# SHIELD4.net
KiCad netlist of a schematic drawn in Altium Designer
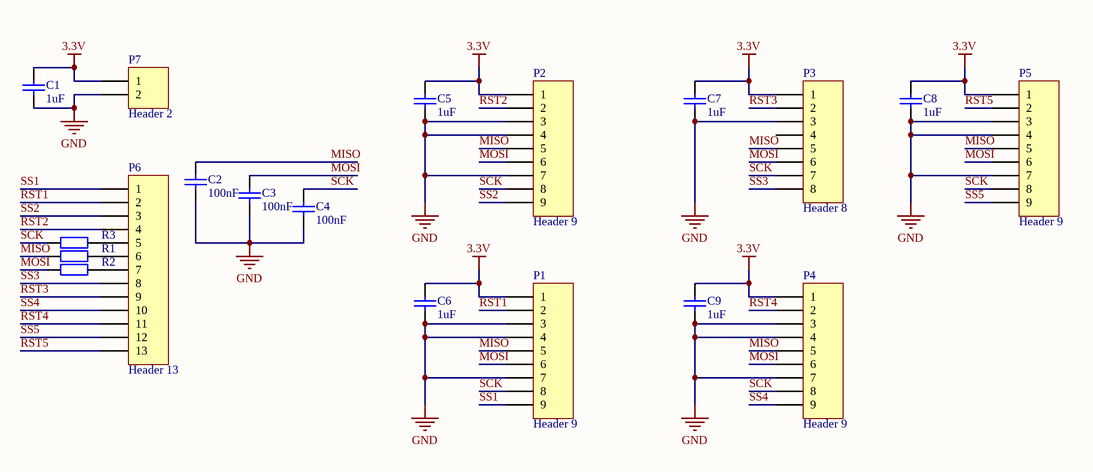
[diagram p0: SHIELD4.SchDoc]

(export (version "E")
  (design (tool "Eeschema 10.0.6"))
  (components
    (comp (ref "C1")
      (value "1uF")
      (footprint "C0805")
      (description "Capacitor")
      (fields (field (name "Comment") "Cap") (field (name "PUBLISHER") "Altium Limited"))
      (libsource (lib "Library") (part "Cap"))
    )
    (comp (ref "C2")
      (value "100nF")
      (footprint "C0805")
      (description "Capacitor")
      (fields (field (name "Comment") "Cap") (field (name "PUBLISHER") "Altium Limited"))
      (libsource (lib "Library") (part "Cap"))
    )
    (comp (ref "C3")
      (value "100nF")
      (footprint "C0805")
      (description "Capacitor")
      (fields (field (name "Comment") "Cap") (field (name "PUBLISHER") "Altium Limited"))
      (libsource (lib "Library") (part "Cap"))
    )
    (comp (ref "C4")
      (value "100nF")
      (footprint "C0805")
      (description "Capacitor")
      (fields (field (name "Comment") "Cap") (field (name "PUBLISHER") "Altium Limited"))
      (libsource (lib "Library") (part "Cap"))
    )
    (comp (ref "C5")
      (value "1uF")
      (footprint "C0805")
      (description "Capacitor")
      (fields (field (name "Comment") "Cap") (field (name "PUBLISHER") "Altium Limited"))
      (libsource (lib "Library") (part "Cap"))
    )
    (comp (ref "C6")
      (value "1uF")
      (footprint "C0805")
      (description "Capacitor")
      (fields (field (name "Comment") "Cap") (field (name "PUBLISHER") "Altium Limited"))
      (libsource (lib "Library") (part "Cap"))
    )
    (comp (ref "C7")
      (value "1uF")
      (footprint "C0805")
      (description "Capacitor")
      (fields (field (name "Comment") "Cap") (field (name "PUBLISHER") "Altium Limited"))
      (libsource (lib "Library") (part "Cap"))
    )
    (comp (ref "C8")
      (value "1uF")
      (footprint "C0805")
      (description "Capacitor")
      (fields (field (name "Comment") "Cap") (field (name "PUBLISHER") "Altium Limited"))
      (libsource (lib "Library") (part "Cap"))
    )
    (comp (ref "C9")
      (value "1uF")
      (footprint "C0805")
      (description "Capacitor")
      (fields (field (name "Comment") "Cap") (field (name "PUBLISHER") "Altium Limited"))
      (libsource (lib "Library") (part "Cap"))
    )
    (comp (ref "P1")
      (value "Header 9")
      (footprint "HDR1X9")
      (description "Header, 9-Pin")
      (fields (field (name "PUBLISHER") "Altium Limited"))
      (libsource (lib "Miscellaneous Connectors") (part "Header 9"))
    )
    (comp (ref "P2")
      (value "Header 9")
      (footprint "HDR1X9")
      (description "Header, 9-Pin")
      (fields (field (name "PUBLISHER") "Altium Limited"))
      (libsource (lib "Miscellaneous Connectors") (part "Header 9"))
    )
    (comp (ref "P3")
      (value "Header 8")
      (footprint "HDR1X8")
      (description "Header, 8-Pin")
      (fields (field (name "PUBLISHER") "Altium Limited"))
      (libsource (lib "Miscellaneous Connectors") (part "Header 8"))
    )
    (comp (ref "P4")
      (value "Header 9")
      (footprint "HDR1X9")
      (description "Header, 9-Pin")
      (fields (field (name "PUBLISHER") "Altium Limited"))
      (libsource (lib "Miscellaneous Connectors") (part "Header 9"))
    )
    (comp (ref "P5")
      (value "Header 9")
      (footprint "HDR1X9")
      (description "Header, 9-Pin")
      (fields (field (name "PUBLISHER") "Altium Limited"))
      (libsource (lib "Miscellaneous Connectors") (part "Header 9"))
    )
    (comp (ref "P6")
      (value "Header 13")
      (footprint "HDR1X13")
      (description "Header, 13-Pin")
      (fields (field (name "PUBLISHER") "Altium Limited"))
      (libsource (lib "Miscellaneous Connectors") (part "Header 13"))
    )
    (comp (ref "P7")
      (value "Header 2")
      (footprint "HDR1X2")
      (description "Header, 2-Pin")
      (fields (field (name "PUBLISHER") "Altium Limited"))
      (libsource (lib "Miscellaneous Connectors") (part "Header 2"))
    )
    (comp (ref "R1")
      (value "Res2")
      (footprint "6-0805_N")
      (description "Resistor")
      (fields (field (name "PUBLISHER") "Altium Limited"))
      (libsource (lib "Library") (part "Res2"))
    )
    (comp (ref "R2")
      (value "Res2")
      (footprint "6-0805_N")
      (description "Resistor")
      (fields (field (name "PUBLISHER") "Altium Limited"))
      (libsource (lib "Library") (part "Res2"))
    )
    (comp (ref "R3")
      (value "Res2")
      (footprint "6-0805_N")
      (description "Resistor")
      (fields (field (name "PUBLISHER") "Altium Limited"))
      (libsource (lib "Library") (part "Res2"))
    )
  )
  (nets
    (net (code "1") (name "/MISO") (class "Default")
      (node (ref "C2") (pin "2") (pinfunction "2_2") (pintype "passive"))
      (node (ref "P1") (pin "5") (pinfunction "5_5") (pintype "passive"))
      (node (ref "P2") (pin "5") (pinfunction "5_5") (pintype "passive"))
      (node (ref "P3") (pin "5") (pinfunction "5_5") (pintype "passive"))
      (node (ref "P4") (pin "5") (pinfunction "5_5") (pintype "passive"))
      (node (ref "P5") (pin "5") (pinfunction "5_5") (pintype "passive"))
      (node (ref "R1") (pin "1") (pinfunction "1_1") (pintype "passive"))
    )
    (net (code "2") (name "/MOSI") (class "Default")
      (node (ref "C3") (pin "1") (pinfunction "1_1") (pintype "passive"))
      (node (ref "P1") (pin "6") (pinfunction "6_6") (pintype "passive"))
      (node (ref "P2") (pin "6") (pinfunction "6_6") (pintype "passive"))
      (node (ref "P3") (pin "6") (pinfunction "6_6") (pintype "passive"))
      (node (ref "P4") (pin "6") (pinfunction "6_6") (pintype "passive"))
      (node (ref "P5") (pin "6") (pinfunction "6_6") (pintype "passive"))
      (node (ref "R2") (pin "1") (pinfunction "1_1") (pintype "passive"))
    )
    (net (code "3") (name "/RST1") (class "Default")
      (node (ref "P1") (pin "2") (pinfunction "2_2") (pintype "passive"))
      (node (ref "P6") (pin "2") (pinfunction "2_2") (pintype "passive"))
    )
    (net (code "4") (name "/RST2") (class "Default")
      (node (ref "P2") (pin "2") (pinfunction "2_2") (pintype "passive"))
      (node (ref "P6") (pin "4") (pinfunction "4_4") (pintype "passive"))
    )
    (net (code "5") (name "/RST3") (class "Default")
      (node (ref "P3") (pin "2") (pinfunction "2_2") (pintype "passive"))
      (node (ref "P6") (pin "9") (pinfunction "9_9") (pintype "passive"))
    )
    (net (code "6") (name "/RST4") (class "Default")
      (node (ref "P4") (pin "2") (pinfunction "2_2") (pintype "passive"))
      (node (ref "P6") (pin "11") (pinfunction "11_11") (pintype "passive"))
    )
    (net (code "7") (name "/RST5") (class "Default")
      (node (ref "P5") (pin "2") (pinfunction "2_2") (pintype "passive"))
      (node (ref "P6") (pin "13") (pinfunction "13_13") (pintype "passive"))
    )
    (net (code "8") (name "/SCK") (class "Default")
      (node (ref "C4") (pin "1") (pinfunction "1_1") (pintype "passive"))
      (node (ref "P1") (pin "8") (pinfunction "8_8") (pintype "passive"))
      (node (ref "P2") (pin "8") (pinfunction "8_8") (pintype "passive"))
      (node (ref "P3") (pin "7") (pinfunction "7_7") (pintype "passive"))
      (node (ref "P4") (pin "8") (pinfunction "8_8") (pintype "passive"))
      (node (ref "P5") (pin "8") (pinfunction "8_8") (pintype "passive"))
      (node (ref "R3") (pin "1") (pinfunction "1_1") (pintype "passive"))
    )
    (net (code "9") (name "/SS1") (class "Default")
      (node (ref "P1") (pin "9") (pinfunction "9_9") (pintype "passive"))
      (node (ref "P6") (pin "1") (pinfunction "1_1") (pintype "passive"))
    )
    (net (code "10") (name "/SS2") (class "Default")
      (node (ref "P2") (pin "9") (pinfunction "9_9") (pintype "passive"))
      (node (ref "P6") (pin "3") (pinfunction "3_3") (pintype "passive"))
    )
    (net (code "11") (name "/SS3") (class "Default")
      (node (ref "P3") (pin "8") (pinfunction "8_8") (pintype "passive"))
      (node (ref "P6") (pin "8") (pinfunction "8_8") (pintype "passive"))
    )
    (net (code "12") (name "/SS4") (class "Default")
      (node (ref "P4") (pin "9") (pinfunction "9_9") (pintype "passive"))
      (node (ref "P6") (pin "10") (pinfunction "10_10") (pintype "passive"))
    )
    (net (code "13") (name "/SS5") (class "Default")
      (node (ref "P5") (pin "9") (pinfunction "9_9") (pintype "passive"))
      (node (ref "P6") (pin "12") (pinfunction "12_12") (pintype "passive"))
    )
    (net (code "14") (name "3.3V") (class "Default")
      (node (ref "C1") (pin "2") (pinfunction "2_2") (pintype "passive"))
      (node (ref "C5") (pin "2") (pinfunction "2_2") (pintype "passive"))
      (node (ref "C6") (pin "2") (pinfunction "2_2") (pintype "passive"))
      (node (ref "C7") (pin "2") (pinfunction "2_2") (pintype "passive"))
      (node (ref "C8") (pin "2") (pinfunction "2_2") (pintype "passive"))
      (node (ref "C9") (pin "2") (pinfunction "2_2") (pintype "passive"))
      (node (ref "P1") (pin "1") (pinfunction "1_1") (pintype "passive"))
      (node (ref "P2") (pin "1") (pinfunction "1_1") (pintype "passive"))
      (node (ref "P3") (pin "1") (pinfunction "1_1") (pintype "passive"))
      (node (ref "P4") (pin "1") (pinfunction "1_1") (pintype "passive"))
      (node (ref "P5") (pin "1") (pinfunction "1_1") (pintype "passive"))
      (node (ref "P7") (pin "1") (pinfunction "1_1") (pintype "passive"))
    )
    (net (code "15") (name "GND") (class "Default")
      (node (ref "C1") (pin "1") (pinfunction "1_1") (pintype "passive"))
      (node (ref "C2") (pin "1") (pinfunction "1_1") (pintype "passive"))
      (node (ref "C3") (pin "2") (pinfunction "2_2") (pintype "passive"))
      (node (ref "C4") (pin "2") (pinfunction "2_2") (pintype "passive"))
      (node (ref "C5") (pin "1") (pinfunction "1_1") (pintype "passive"))
      (node (ref "C6") (pin "1") (pinfunction "1_1") (pintype "passive"))
      (node (ref "C7") (pin "1") (pinfunction "1_1") (pintype "passive"))
      (node (ref "C8") (pin "1") (pinfunction "1_1") (pintype "passive"))
      (node (ref "C9") (pin "1") (pinfunction "1_1") (pintype "passive"))
      (node (ref "P1") (pin "3") (pinfunction "3_3") (pintype "passive"))
      (node (ref "P1") (pin "4") (pinfunction "4_4") (pintype "passive"))
      (node (ref "P1") (pin "7") (pinfunction "7_7") (pintype "passive"))
      (node (ref "P2") (pin "3") (pinfunction "3_3") (pintype "passive"))
      (node (ref "P2") (pin "4") (pinfunction "4_4") (pintype "passive"))
      (node (ref "P2") (pin "7") (pinfunction "7_7") (pintype "passive"))
      (node (ref "P3") (pin "3") (pinfunction "3_3") (pintype "passive"))
      (node (ref "P4") (pin "3") (pinfunction "3_3") (pintype "passive"))
      (node (ref "P4") (pin "4") (pinfunction "4_4") (pintype "passive"))
      (node (ref "P4") (pin "7") (pinfunction "7_7") (pintype "passive"))
      (node (ref "P5") (pin "3") (pinfunction "3_3") (pintype "passive"))
      (node (ref "P5") (pin "4") (pinfunction "4_4") (pintype "passive"))
      (node (ref "P5") (pin "7") (pinfunction "7_7") (pintype "passive"))
      (node (ref "P7") (pin "2") (pinfunction "2_2") (pintype "passive"))
    )
    (net (code "16") (name "Net-(P6-Pad5)") (class "Default")
      (node (ref "P6") (pin "5") (pinfunction "5_5") (pintype "passive"))
      (node (ref "R3") (pin "2") (pinfunction "2_2") (pintype "passive"))
    )
    (net (code "17") (name "Net-(P6-Pad6)") (class "Default")
      (node (ref "P6") (pin "6") (pinfunction "6_6") (pintype "passive"))
      (node (ref "R1") (pin "2") (pinfunction "2_2") (pintype "passive"))
    )
    (net (code "18") (name "Net-(P6-Pad7)") (class "Default")
      (node (ref "P6") (pin "7") (pinfunction "7_7") (pintype "passive"))
      (node (ref "R2") (pin "2") (pinfunction "2_2") (pintype "passive"))
    )
    (net (code "19") (name "unconnected-(P3-Pad4)") (class "Default")
      (node (ref "P3") (pin "4") (pinfunction "4_4") (pintype "passive"))
    )
  )
)
